# FanControl.net
KiCad netlist of a schematic drawn in Altium Designer
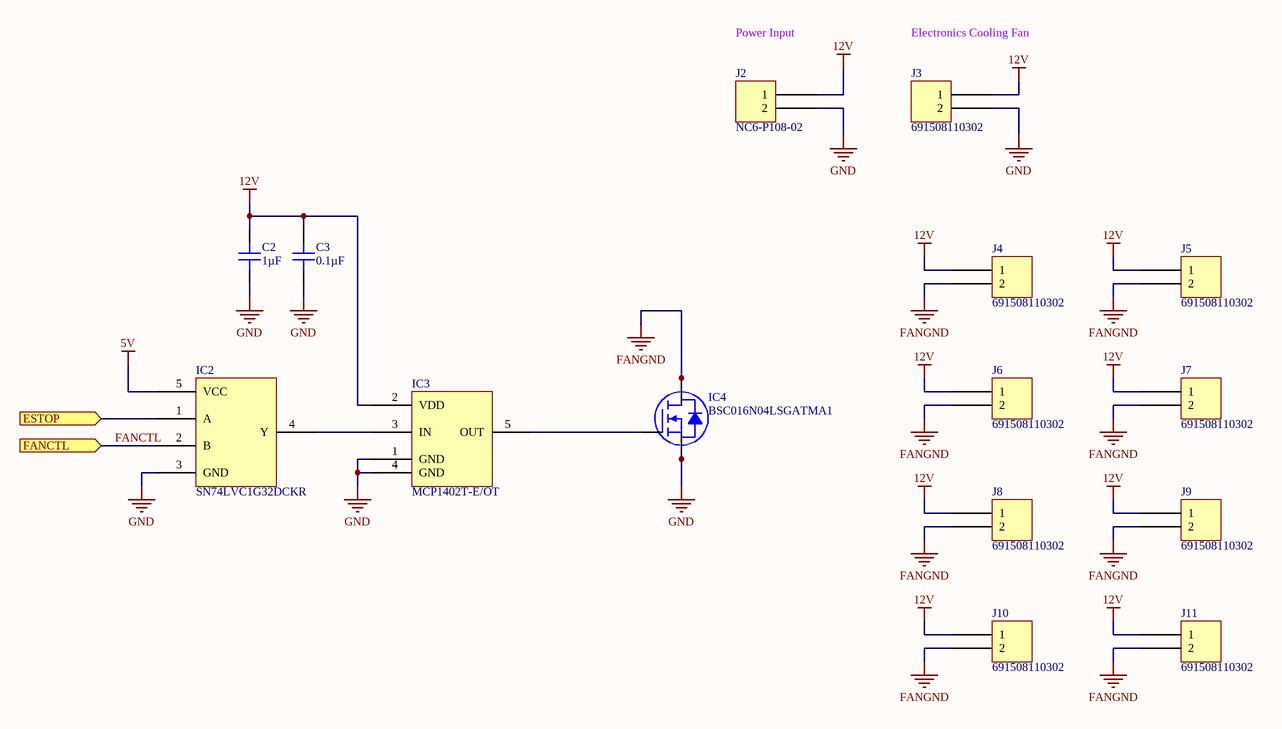
[diagram p0: FanControl.SchDoc]

(export (version "E")
  (design (tool "Eeschema 10.0.6"))
  (components
    (comp (ref "C2")
      (value "1µF")
      (footprint "CAP 0603_1608")
      (description "CAP CER 1UF 25V X5R 0603")
      (fields (field (name "PART NUMBER") "CC0603KRX5R8BB105") (field (name "MANUFACTURER") "Yageo"))
      (libsource (lib "Celestial Altium Library - altium_library") (part "Capacitor"))
    )
    (comp (ref "C3")
      (value "0.1µF")
      (footprint "CAP 0603_1608")
      (description "CAP CER 0.1UF 50V X7R 0603")
      (fields (field (name "PART NUMBER") "06035C104JAT4A") (field (name "MANUFACTURER") "AVX Corporation"))
      (libsource (lib "Celestial Altium Library - altium_library") (part "Capacitor"))
    )
    (comp (ref "IC2")
      (value "SN74LVC1G32DCKR")
      (footprint "TI SC70-6 DCK")
      (description "IC GATE OR 1CH 2-INP SC70-5")
      (fields (field (name "MANUFACTURER") "Texas Instruments"))
      (libsource (lib "Celestial Altium Library - altium_library") (part "TI SN74LVC1G32"))
    )
    (comp (ref "IC3")
      (value "MCP1402T-E/OT")
      (footprint "MICROCHIP SOT-23-5 OT")
      (description "IC GATE DRVR LOW-SIDE SOT23-5")
      (fields (field (name "MANUFACTURER") "Microchip Technology"))
      (libsource (lib "Celestial Altium Library - altium_library") (part "MICROCHIP MCP1402"))
    )
    (comp (ref "IC4")
      (value "BSC016N04LSGATMA1")
      (footprint "INFINEON PG-TDSON-8")
      (description "MOSFET N-CH 40V 100A TDSON-8")
      (fields (field (name "MANUFACTURER") "Infineon Technologies"))
      (libsource (lib "Celestial Altium Library - altium_library") (part "INFINEON BSC MOSFET N-CH"))
    )
    (comp (ref "J2")
      (value "NC6-P108-02")
      (footprint "TE NC6-P108-02")
      (description "CONN BARRIER STRIP 2CIRC 0.375\"")
      (fields (field (name "MANUFACTURER") "TE Connectivity AMP Connectors"))
      (libsource (lib "") (part "2 Pin_1"))
    )
    (comp (ref "J3")
      (value "691508110302")
      (footprint "WURTH 691508110302")
      (description "TERM BLOCK 2POS 3.5MM SMD")
      (fields (field (name "MANUFACTURER") "Würth Elektronik") (field (name "VOLTAGE") "300V"))
      (libsource (lib "") (part "2 Pin_1"))
    )
    (comp (ref "J4")
      (value "691508110302")
      (footprint "WURTH 691508110302")
      (description "TERM BLOCK 2POS 3.5MM SMD")
      (fields (field (name "MANUFACTURER") "Würth Elektronik") (field (name "VOLTAGE") "300V"))
      (libsource (lib "Celestial Altium Library - altium_library") (part "2 Pin"))
    )
    (comp (ref "J5")
      (value "691508110302")
      (footprint "WURTH 691508110302")
      (description "TERM BLOCK 2POS 3.5MM SMD")
      (fields (field (name "MANUFACTURER") "Würth Elektronik") (field (name "VOLTAGE") "300V"))
      (libsource (lib "Celestial Altium Library - altium_library") (part "2 Pin"))
    )
    (comp (ref "J6")
      (value "691508110302")
      (footprint "WURTH 691508110302")
      (description "TERM BLOCK 2POS 3.5MM SMD")
      (fields (field (name "MANUFACTURER") "Würth Elektronik") (field (name "VOLTAGE") "300V"))
      (libsource (lib "Celestial Altium Library - altium_library") (part "2 Pin"))
    )
    (comp (ref "J7")
      (value "691508110302")
      (footprint "WURTH 691508110302")
      (description "TERM BLOCK 2POS 3.5MM SMD")
      (fields (field (name "MANUFACTURER") "Würth Elektronik") (field (name "VOLTAGE") "300V"))
      (libsource (lib "Celestial Altium Library - altium_library") (part "2 Pin"))
    )
    (comp (ref "J8")
      (value "691508110302")
      (footprint "WURTH 691508110302")
      (description "TERM BLOCK 2POS 3.5MM SMD")
      (fields (field (name "MANUFACTURER") "Würth Elektronik") (field (name "VOLTAGE") "300V"))
      (libsource (lib "Celestial Altium Library - altium_library") (part "2 Pin"))
    )
    (comp (ref "J9")
      (value "691508110302")
      (footprint "WURTH 691508110302")
      (description "TERM BLOCK 2POS 3.5MM SMD")
      (fields (field (name "MANUFACTURER") "Würth Elektronik") (field (name "VOLTAGE") "300V"))
      (libsource (lib "Celestial Altium Library - altium_library") (part "2 Pin"))
    )
    (comp (ref "J10")
      (value "691508110302")
      (footprint "WURTH 691508110302")
      (description "TERM BLOCK 2POS 3.5MM SMD")
      (fields (field (name "MANUFACTURER") "Würth Elektronik") (field (name "VOLTAGE") "300V"))
      (libsource (lib "Celestial Altium Library - altium_library") (part "2 Pin"))
    )
    (comp (ref "J11")
      (value "691508110302")
      (footprint "WURTH 691508110302")
      (description "TERM BLOCK 2POS 3.5MM SMD")
      (fields (field (name "MANUFACTURER") "Würth Elektronik") (field (name "VOLTAGE") "300V"))
      (libsource (lib "Celestial Altium Library - altium_library") (part "2 Pin"))
    )
  )
  (nets
    (net (code "1") (name "/ESTOP") (class "Default")
      (node (ref "IC2") (pin "1") (pinfunction "A_1") (pintype "passive"))
    )
    (net (code "2") (name "/FANCTL") (class "Default")
      (node (ref "IC2") (pin "2") (pinfunction "B_2") (pintype "passive"))
    )
    (net (code "3") (name "5V") (class "Default")
      (node (ref "IC2") (pin "5") (pinfunction "VCC_5") (pintype "passive"))
    )
    (net (code "4") (name "12V") (class "Default")
      (node (ref "C2") (pin "2") (pinfunction "2_2") (pintype "passive"))
      (node (ref "C3") (pin "2") (pinfunction "2_2") (pintype "passive"))
      (node (ref "IC3") (pin "2") (pinfunction "VDD_2") (pintype "passive"))
      (node (ref "J10") (pin "1") (pinfunction "1_1") (pintype "passive"))
      (node (ref "J11") (pin "1") (pinfunction "1_1") (pintype "passive"))
      (node (ref "J2") (pin "1") (pinfunction "1_1") (pintype "passive"))
      (node (ref "J3") (pin "1") (pinfunction "1_1") (pintype "passive"))
      (node (ref "J4") (pin "1") (pinfunction "1_1") (pintype "passive"))
      (node (ref "J5") (pin "1") (pinfunction "1_1") (pintype "passive"))
      (node (ref "J6") (pin "1") (pinfunction "1_1") (pintype "passive"))
      (node (ref "J7") (pin "1") (pinfunction "1_1") (pintype "passive"))
      (node (ref "J8") (pin "1") (pinfunction "1_1") (pintype "passive"))
      (node (ref "J9") (pin "1") (pinfunction "1_1") (pintype "passive"))
    )
    (net (code "5") (name "FANGND") (class "Default")
      (node (ref "IC4") (pin "5") (pinfunction "D_5") (pintype "passive"))
      (node (ref "IC4") (pin "6") (pinfunction "D_6") (pintype "passive"))
      (node (ref "IC4") (pin "7") (pinfunction "D_7") (pintype "passive"))
      (node (ref "IC4") (pin "8") (pinfunction "D_8") (pintype "passive"))
      (node (ref "J10") (pin "2") (pinfunction "2_2") (pintype "passive"))
      (node (ref "J11") (pin "2") (pinfunction "2_2") (pintype "passive"))
      (node (ref "J4") (pin "2") (pinfunction "2_2") (pintype "passive"))
      (node (ref "J5") (pin "2") (pinfunction "2_2") (pintype "passive"))
      (node (ref "J6") (pin "2") (pinfunction "2_2") (pintype "passive"))
      (node (ref "J7") (pin "2") (pinfunction "2_2") (pintype "passive"))
      (node (ref "J8") (pin "2") (pinfunction "2_2") (pintype "passive"))
      (node (ref "J9") (pin "2") (pinfunction "2_2") (pintype "passive"))
    )
    (net (code "6") (name "GND") (class "Default")
      (node (ref "C2") (pin "1") (pinfunction "1_1") (pintype "passive"))
      (node (ref "C3") (pin "1") (pinfunction "1_1") (pintype "passive"))
      (node (ref "IC2") (pin "3") (pinfunction "GND_3") (pintype "passive"))
      (node (ref "IC3") (pin "1") (pinfunction "GND_1") (pintype "passive"))
      (node (ref "IC3") (pin "4") (pinfunction "GND_4") (pintype "passive"))
      (node (ref "IC4") (pin "1") (pinfunction "S_1") (pintype "passive"))
      (node (ref "IC4") (pin "2") (pinfunction "S_2") (pintype "passive"))
      (node (ref "IC4") (pin "3") (pinfunction "S_3") (pintype "passive"))
      (node (ref "J2") (pin "2") (pinfunction "2_2") (pintype "passive"))
      (node (ref "J3") (pin "2") (pinfunction "2_2") (pintype "passive"))
    )
    (net (code "7") (name "Net-(IC2-Y)") (class "Default")
      (node (ref "IC2") (pin "4") (pinfunction "Y_4") (pintype "passive"))
      (node (ref "IC3") (pin "3") (pinfunction "IN_3") (pintype "passive"))
    )
    (net (code "8") (name "Net-(IC3-OUT)") (class "Default")
      (node (ref "IC3") (pin "5") (pinfunction "OUT_5") (pintype "passive"))
      (node (ref "IC4") (pin "4") (pinfunction "G_4") (pintype "passive"))
    )
  )
)
